# untitled2.net
KiCad netlist of a schematic drawn in EAGLE
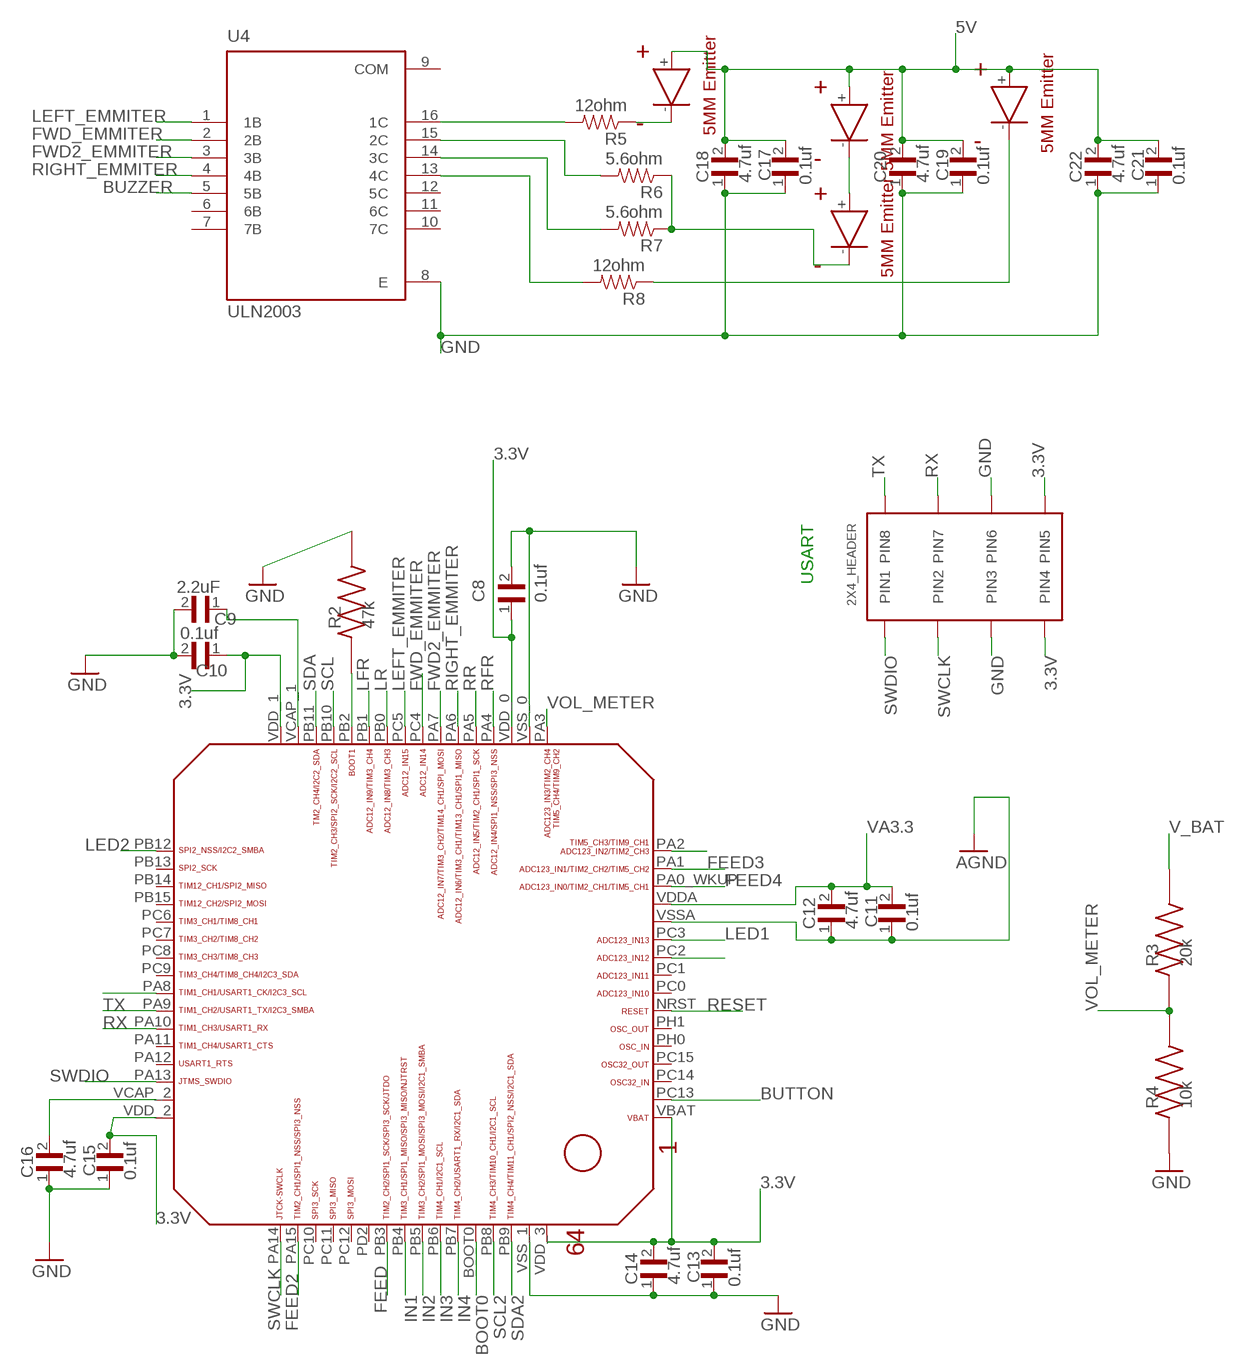
[diagram p0: schematic, sheet 1, part 1 of 2]
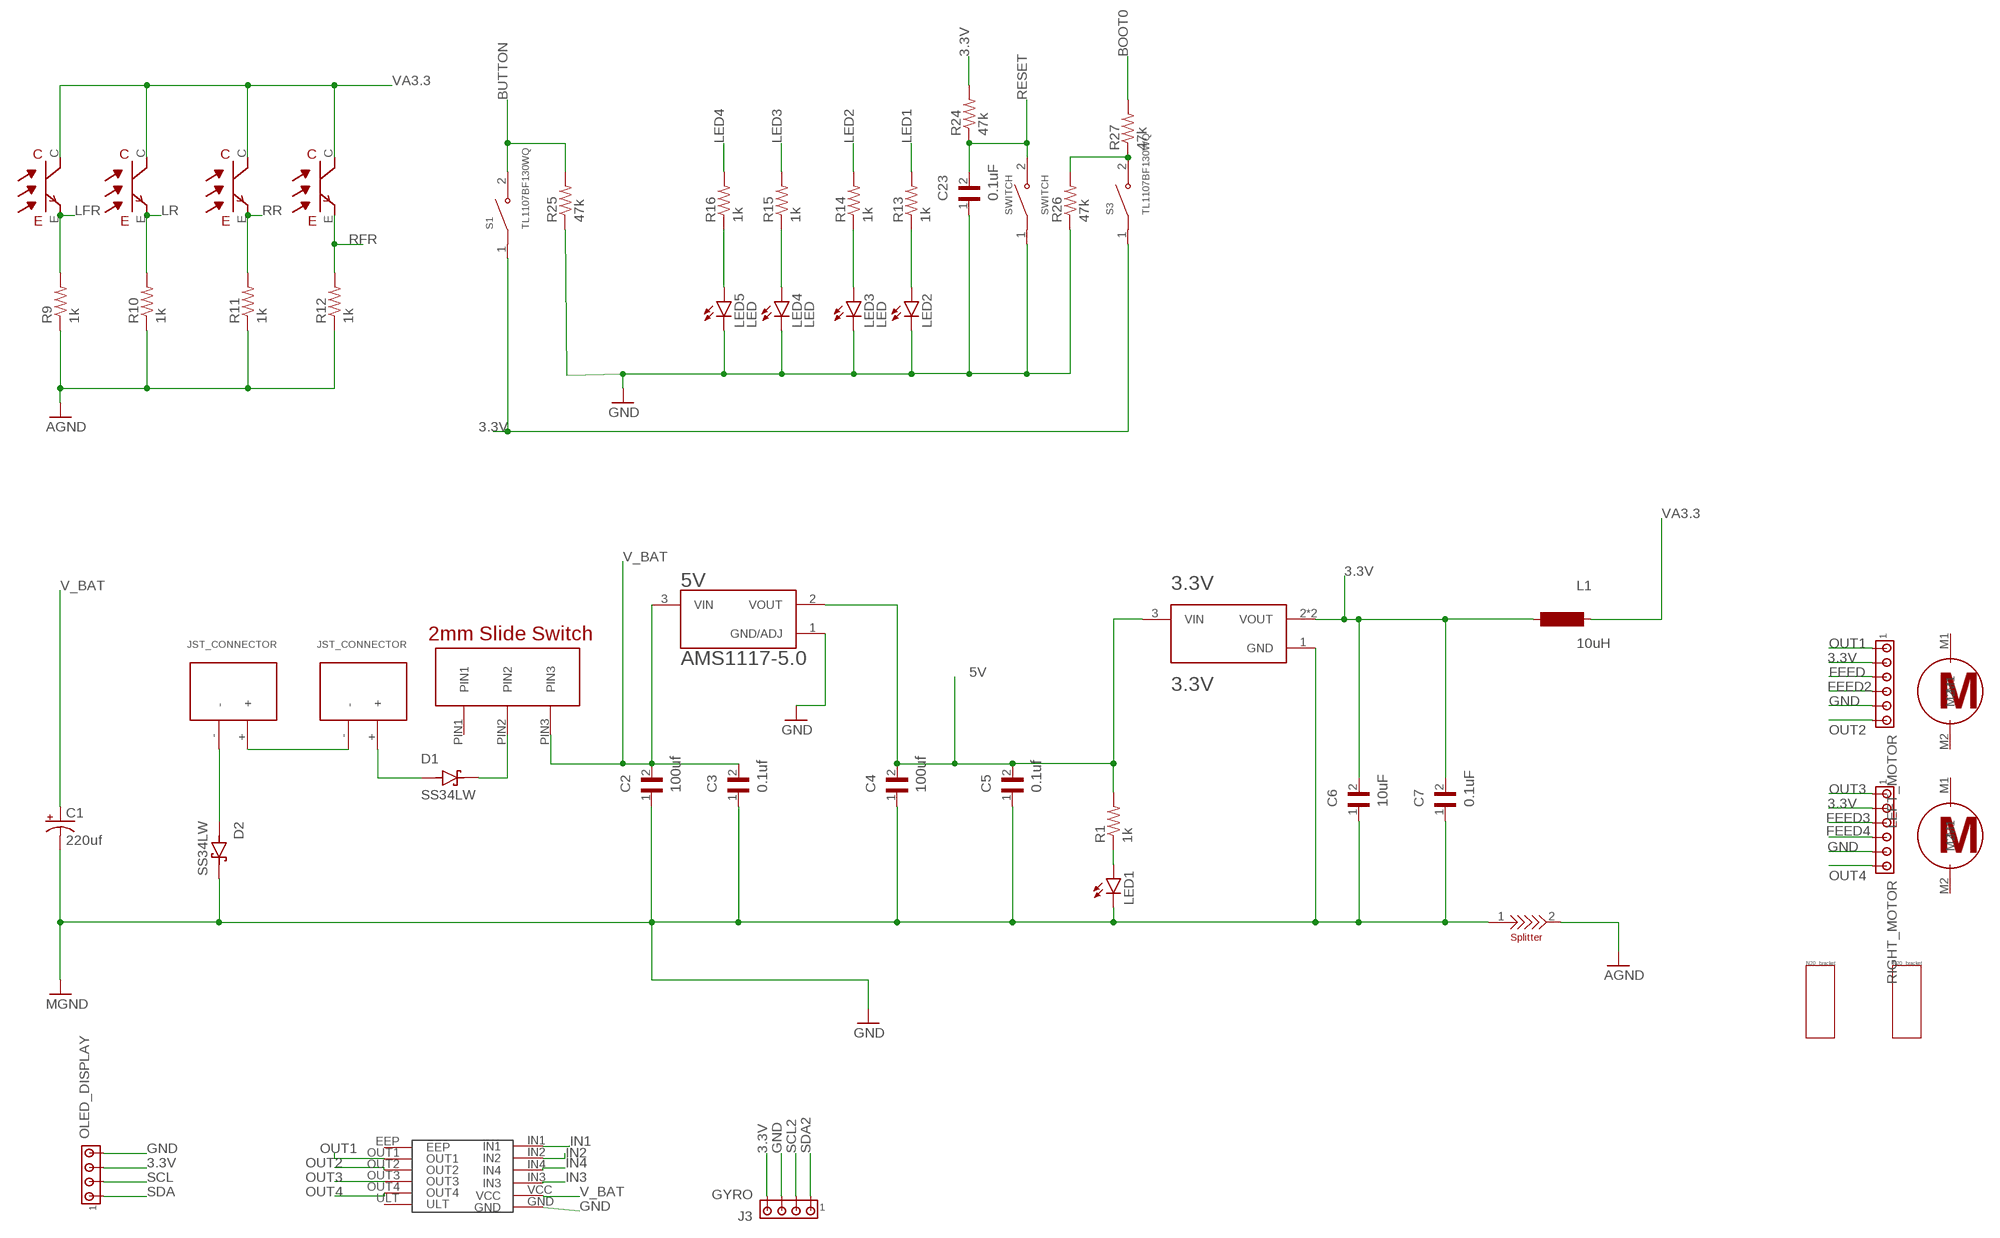
[diagram p1: schematic, sheet 1, part 2 of 2]

(export (version "E")
  (design (tool "Eeschema 10.0.6"))
  (components
    (comp (ref "3.3V")
      (value "3.3V")
      (footprint "eagle-import:SOT230P700X180-4N")
      (fields (field (name "MF") "STMicroelectronics") (field (name "MP") "LDL1117S33R"))
      (libsource (lib "eagle-import") (part "LDL1117S33R"))
    )
    (comp (ref "5V")
      (value "AMS1117-5.0")
      (footprint "eagle-import:SOT229P700X180-4N")
      (fields (field (name "MF") "Advanced Monolithic Systems"))
      (libsource (lib "eagle-import") (part "AMS1117-5.0"))
    )
    (comp (ref "C1")
      (value "220uf")
      (footprint "eagle-import:EIA3216")
      (libsource (lib "eagle-import") (part "CAP_POL1206"))
    )
    (comp (ref "C2")
      (value "100uf")
      (footprint "eagle-import:CAPC0603X35N")
      (fields (field (name "MF") "Murata") (field (name "MP") "GRM033R60J105MEA2D"))
      (libsource (lib "eagle-import") (part "GRM033R60J105MEA2D"))
    )
    (comp (ref "C3")
      (value "0.1uf")
      (footprint "eagle-import:CAPC0603X35N")
      (fields (field (name "MF") "Murata") (field (name "MP") "GRM033R60J105MEA2D"))
      (libsource (lib "eagle-import") (part "GRM033R60J105MEA2D"))
    )
    (comp (ref "C4")
      (value "100uf")
      (footprint "eagle-import:CAPC0603X35N")
      (fields (field (name "MF") "Murata") (field (name "MP") "GRM033R60J105MEA2D"))
      (libsource (lib "eagle-import") (part "GRM033R60J105MEA2D"))
    )
    (comp (ref "C5")
      (value "0.1uf")
      (footprint "eagle-import:CAPC0603X35N")
      (fields (field (name "MF") "Murata") (field (name "MP") "GRM033R60J105MEA2D"))
      (libsource (lib "eagle-import") (part "GRM033R60J105MEA2D"))
    )
    (comp (ref "C6")
      (value "10uF")
      (footprint "eagle-import:CAPC0603X35N")
      (fields (field (name "MF") "Murata") (field (name "MP") "GRM033R60J105MEA2D"))
      (libsource (lib "eagle-import") (part "GRM033R60J105MEA2D"))
    )
    (comp (ref "C7")
      (value "0.1uF")
      (footprint "eagle-import:CAPC0603X35N")
      (fields (field (name "MF") "Murata") (field (name "MP") "GRM033R60J105MEA2D"))
      (libsource (lib "eagle-import") (part "GRM033R60J105MEA2D"))
    )
    (comp (ref "C8")
      (value "0.1uf")
      (footprint "eagle-import:CAPC0603X35N")
      (fields (field (name "MF") "Murata") (field (name "MP") "GRM033R60J105MEA2D"))
      (libsource (lib "eagle-import") (part "GRM033R60J105MEA2D"))
    )
    (comp (ref "C9")
      (value "2.2uF")
      (footprint "eagle-import:CAPC0603X35N")
      (fields (field (name "MF") "Murata") (field (name "MP") "GRM033R60J105MEA2D"))
      (libsource (lib "eagle-import") (part "GRM033R60J105MEA2D"))
    )
    (comp (ref "C10")
      (value "0.1uf")
      (footprint "eagle-import:CAPC0603X35N")
      (fields (field (name "MF") "Murata") (field (name "MP") "GRM033R60J105MEA2D"))
      (libsource (lib "eagle-import") (part "GRM033R60J105MEA2D"))
    )
    (comp (ref "C11")
      (value "0.1uf")
      (footprint "eagle-import:CAPC0603X35N")
      (fields (field (name "MF") "Murata") (field (name "MP") "GRM033R60J105MEA2D"))
      (libsource (lib "eagle-import") (part "GRM033R60J105MEA2D"))
    )
    (comp (ref "C12")
      (value "4.7uf")
      (footprint "eagle-import:CAPC0603X35N")
      (fields (field (name "MF") "Murata") (field (name "MP") "GRM033R60J105MEA2D"))
      (libsource (lib "eagle-import") (part "GRM033R60J105MEA2D"))
    )
    (comp (ref "C13")
      (value "0.1uf")
      (footprint "eagle-import:CAPC0603X35N")
      (fields (field (name "MF") "Murata") (field (name "MP") "GRM033R60J105MEA2D"))
      (libsource (lib "eagle-import") (part "GRM033R60J105MEA2D"))
    )
    (comp (ref "C14")
      (value "4.7uf")
      (footprint "eagle-import:CAPC0603X35N")
      (fields (field (name "MF") "Murata") (field (name "MP") "GRM033R60J105MEA2D"))
      (libsource (lib "eagle-import") (part "GRM033R60J105MEA2D"))
    )
    (comp (ref "C15")
      (value "0.1uf")
      (footprint "eagle-import:CAPC0603X35N")
      (fields (field (name "MF") "Murata") (field (name "MP") "GRM033R60J105MEA2D"))
      (libsource (lib "eagle-import") (part "GRM033R60J105MEA2D"))
    )
    (comp (ref "C16")
      (value "4.7uf")
      (footprint "eagle-import:CAPC0603X35N")
      (fields (field (name "MF") "Murata") (field (name "MP") "GRM033R60J105MEA2D"))
      (libsource (lib "eagle-import") (part "GRM033R60J105MEA2D"))
    )
    (comp (ref "C17")
      (value "0.1uf")
      (footprint "eagle-import:CAPC0603X35N")
      (fields (field (name "MF") "Murata") (field (name "MP") "GRM033R60J105MEA2D"))
      (libsource (lib "eagle-import") (part "GRM033R60J105MEA2D"))
    )
    (comp (ref "C18")
      (value "4.7uf")
      (footprint "eagle-import:CAPC0603X35N")
      (fields (field (name "MF") "Murata") (field (name "MP") "GRM033R60J105MEA2D"))
      (libsource (lib "eagle-import") (part "GRM033R60J105MEA2D"))
    )
    (comp (ref "C19")
      (value "0.1uf")
      (footprint "eagle-import:CAPC0603X35N")
      (fields (field (name "MF") "Murata") (field (name "MP") "GRM033R60J105MEA2D"))
      (libsource (lib "eagle-import") (part "GRM033R60J105MEA2D"))
    )
    (comp (ref "C20")
      (value "4.7uf")
      (footprint "eagle-import:CAPC0603X35N")
      (fields (field (name "MF") "Murata") (field (name "MP") "GRM033R60J105MEA2D"))
      (libsource (lib "eagle-import") (part "GRM033R60J105MEA2D"))
    )
    (comp (ref "C21")
      (value "0.1uf")
      (footprint "eagle-import:CAPC0603X35N")
      (fields (field (name "MF") "Murata") (field (name "MP") "GRM033R60J105MEA2D"))
      (libsource (lib "eagle-import") (part "GRM033R60J105MEA2D"))
    )
    (comp (ref "C22")
      (value "4.7uf")
      (footprint "eagle-import:CAPC0603X35N")
      (fields (field (name "MF") "Murata") (field (name "MP") "GRM033R60J105MEA2D"))
      (libsource (lib "eagle-import") (part "GRM033R60J105MEA2D"))
    )
    (comp (ref "C23")
      (value "0.1uF")
      (footprint "eagle-import:CAPC0603X35N")
      (fields (field (name "MF") "Murata") (field (name "MP") "GRM033R60J105MEA2D"))
      (libsource (lib "eagle-import") (part "GRM033R60J105MEA2D"))
    )
    (comp (ref "D1")
      (value "SS34LW")
      (footprint "eagle-import:SODFL3718X102N")
      (fields (field (name "MF") "Taiwan Semiconductor"))
      (libsource (lib "eagle-import") (part "SS34LW"))
    )
    (comp (ref "D2")
      (value "SS34LW")
      (footprint "eagle-import:SODFL3718X102N")
      (fields (field (name "MF") "Taiwan Semiconductor"))
      (libsource (lib "eagle-import") (part "SS34LW"))
    )
    (comp (ref "EMMI1")
      (value "EMITTER")
      (footprint "eagle-import:EMITTER")
      (libsource (lib "eagle-import") (part "EMITTER"))
    )
    (comp (ref "J3")
      (value "GYRO")
      (footprint "eagle-import:10X04MTA")
      (libsource (lib "eagle-import") (part "MTA04-100"))
    )
    (comp (ref "L1")
      (value "10uH")
      (footprint "eagle-import:MS42")
      (libsource (lib "eagle-import") (part "MS42"))
    )
    (comp (ref "LED1")
      (value "LEDCHIPLED_0805")
      (footprint "eagle-import:CHIPLED_0805")
      (libsource (lib "eagle-import") (part "LEDCHIPLED_0805"))
    )
    (comp (ref "LED2")
      (value "LEDCHIPLED_0805")
      (footprint "eagle-import:CHIPLED_0805")
      (libsource (lib "eagle-import") (part "LEDCHIPLED_0805"))
    )
    (comp (ref "LED3")
      (value "LED")
      (footprint "eagle-import:CHIPLED_0805")
      (libsource (lib "eagle-import") (part "LEDCHIPLED_0805"))
    )
    (comp (ref "LED4")
      (value "LED")
      (footprint "eagle-import:CHIPLED_0805")
      (libsource (lib "eagle-import") (part "LEDCHIPLED_0805"))
    )
    (comp (ref "LED5")
      (value "LED")
      (footprint "eagle-import:CHIPLED_0805")
      (libsource (lib "eagle-import") (part "LEDCHIPLED_0805"))
    )
    (comp (ref "LEFT_MOTOR")
      (value "MTA06-100")
      (footprint "eagle-import:10X06MTA")
      (libsource (lib "eagle-import") (part "MTA06-100"))
    )
    (comp (ref "OLED_DISPLAY")
      (value "MTA04-100")
      (footprint "eagle-import:10X04MTA")
      (libsource (lib "eagle-import") (part "MTA04-100"))
    )
    (comp (ref "R1")
      (value "1k")
      (footprint "eagle-import:0603-RES")
      (libsource (lib "eagle-import") (part "RESISTOR0603-RES"))
    )
    (comp (ref "R2")
      (value "47k")
      (footprint "eagle-import:RES_ERJU01F3570C")
      (fields (field (name "MF") "Panasonic") (field (name "MP") "ERJ-U01F3570C"))
      (libsource (lib "eagle-import") (part "ERJU01F3570C"))
    )
    (comp (ref "R3")
      (value "20k")
      (footprint "eagle-import:RES_ERJU01F3570C")
      (fields (field (name "MF") "Panasonic") (field (name "MP") "ERJ-U01F3570C"))
      (libsource (lib "eagle-import") (part "ERJU01F3570C"))
    )
    (comp (ref "R4")
      (value "10k")
      (footprint "eagle-import:RES_ERJU01F3570C")
      (fields (field (name "MF") "Panasonic") (field (name "MP") "ERJ-U01F3570C"))
      (libsource (lib "eagle-import") (part "ERJU01F3570C"))
    )
    (comp (ref "R5")
      (value "12ohm")
      (footprint "eagle-import:0603-RES")
      (libsource (lib "eagle-import") (part "RESISTOR0603-RES"))
    )
    (comp (ref "R6")
      (value "5.6ohm")
      (footprint "eagle-import:0603-RES")
      (libsource (lib "eagle-import") (part "RESISTOR0603-RES"))
    )
    (comp (ref "R7")
      (value "5.6ohm")
      (footprint "eagle-import:0603-RES")
      (libsource (lib "eagle-import") (part "RESISTOR0603-RES"))
    )
    (comp (ref "R8")
      (value "12ohm")
      (footprint "eagle-import:0603-RES")
      (libsource (lib "eagle-import") (part "RESISTOR0603-RES"))
    )
    (comp (ref "R9")
      (value "1k")
      (footprint "eagle-import:0603-RES")
      (libsource (lib "eagle-import") (part "RESISTOR0603-RES"))
    )
    (comp (ref "R10")
      (value "1k")
      (footprint "eagle-import:0603-RES")
      (libsource (lib "eagle-import") (part "RESISTOR0603-RES"))
    )
    (comp (ref "R11")
      (value "1k")
      (footprint "eagle-import:0603-RES")
      (libsource (lib "eagle-import") (part "RESISTOR0603-RES"))
    )
    (comp (ref "R12")
      (value "1k")
      (footprint "eagle-import:0603-RES")
      (libsource (lib "eagle-import") (part "RESISTOR0603-RES"))
    )
    (comp (ref "R13")
      (value "1k")
      (footprint "eagle-import:0603-RES")
      (libsource (lib "eagle-import") (part "RESISTOR0603-RES"))
    )
    (comp (ref "R14")
      (value "1k")
      (footprint "eagle-import:0603-RES")
      (libsource (lib "eagle-import") (part "RESISTOR0603-RES"))
    )
    (comp (ref "R15")
      (value "1k")
      (footprint "eagle-import:0603-RES")
      (libsource (lib "eagle-import") (part "RESISTOR0603-RES"))
    )
    (comp (ref "R16")
      (value "1k")
      (footprint "eagle-import:0603-RES")
      (libsource (lib "eagle-import") (part "RESISTOR0603-RES"))
    )
    (comp (ref "R24")
      (value "47k")
      (footprint "eagle-import:0603-RES")
      (libsource (lib "eagle-import") (part "RESISTOR0603-RES"))
    )
    (comp (ref "R25")
      (value "47k")
      (footprint "eagle-import:0603-RES")
      (libsource (lib "eagle-import") (part "RESISTOR0603-RES"))
    )
    (comp (ref "R26")
      (value "47k")
      (footprint "eagle-import:0603-RES")
      (libsource (lib "eagle-import") (part "RESISTOR0603-RES"))
    )
    (comp (ref "R27")
      (value "47k")
      (footprint "eagle-import:0603-RES")
      (libsource (lib "eagle-import") (part "RESISTOR0603-RES"))
    )
    (comp (ref "RIGHT_MOTOR")
      (value "MTA06-100")
      (footprint "eagle-import:10X06MTA")
      (libsource (lib "eagle-import") (part "MTA06-100"))
    )
    (comp (ref "S1")
      (value "TL1107BF130WQ")
      (footprint "eagle-import:SW_TL1107BF130WQ")
      (fields (field (name "MF") "E-Switch"))
      (libsource (lib "eagle-import") (part "TL1107BF130WQ"))
    )
    (comp (ref "S3")
      (value "TL1107BF130WQ")
      (footprint "eagle-import:SW_TL1107BF130WQ")
      (fields (field (name "MF") "E-Switch"))
      (libsource (lib "eagle-import") (part "TL1107BF130WQ"))
    )
    (comp (ref "STM32F405RGT6")
      (value "STM32F405/415_LQFP64")
      (footprint "eagle-import:STM32F405_415_LQFP64")
      (libsource (lib "eagle-import") (part "STM32F405/415_LQFP64"))
    )
    (comp (ref "SWITCH")
      (value "SWITCH")
      (footprint "eagle-import:SW_TL1107BF130WQ")
      (fields (field (name "MF") "E-Switch") (field (name "MP") "TL1107BF130WQ"))
      (libsource (lib "eagle-import") (part "TL1107BF130WQ"))
    )
    (comp (ref "U$1")
      (value "N20_BRACKET")
      (footprint "eagle-import:BRACKER")
      (libsource (lib "eagle-import") (part "N20_BRACKET"))
    )
    (comp (ref "U$2")
      (value "MOTOR_N20")
      (footprint "eagle-import:MOTOR_N20")
      (libsource (lib "eagle-import") (part "MOTOR_N20"))
    )
    (comp (ref "U$3")
      (value "MOTOR_N20")
      (footprint "eagle-import:MOTOR_N20")
      (libsource (lib "eagle-import") (part "MOTOR_N20"))
    )
    (comp (ref "U$4")
      (value "N20_BRACKET")
      (footprint "eagle-import:BRACKER")
      (libsource (lib "eagle-import") (part "N20_BRACKET"))
    )
    (comp (ref "U$5")
      (value "JST_CONNECTOR_FEMALE")
      (footprint "eagle-import:JST_CONNECTOR_FEMALE")
      (libsource (lib "eagle-import") (part "JST_CONNECTOR_FEMALE"))
    )
    (comp (ref "U$6")
      (value "JST_CONNECTOR_FEMALE")
      (footprint "eagle-import:JST_CONNECTOR_FEMALE")
      (libsource (lib "eagle-import") (part "JST_CONNECTOR_FEMALE"))
    )
    (comp (ref "U$8")
      (value "2MMS_SLIDE_SWITCH")
      (footprint "eagle-import:2MMS_SLIDE_SWITCH")
      (libsource (lib "eagle-import") (part "2MMS_SLIDE_SWITCH"))
    )
    (comp (ref "U$9")
      (value "SPLITTER")
      (footprint "eagle-import:SPLITTER")
      (libsource (lib "eagle-import") (part "SPLITTER"))
    )
    (comp (ref "U$10")
      (value "2X3_HEADER")
      (footprint "eagle-import:2X3_HEADER")
      (libsource (lib "eagle-import") (part "2X3_HEADER"))
    )
    (comp (ref "U$11")
      (value "DRV8833")
      (footprint "eagle-import:DRV8833")
      (libsource (lib "eagle-import") (part "DRV8833"))
    )
    (comp (ref "U$12")
      (value "RECEIVER")
      (footprint "eagle-import:RECEIVER")
      (libsource (lib "eagle-import") (part "RECEIVER"))
    )
    (comp (ref "U$13")
      (value "EMITTER")
      (footprint "eagle-import:EMITTER")
      (libsource (lib "eagle-import") (part "EMITTER"))
    )
    (comp (ref "U$14")
      (value "EMITTER")
      (footprint "eagle-import:EMITTER")
      (libsource (lib "eagle-import") (part "EMITTER"))
    )
    (comp (ref "U$15")
      (value "EMITTER")
      (footprint "eagle-import:EMITTER")
      (libsource (lib "eagle-import") (part "EMITTER"))
    )
    (comp (ref "U$16")
      (value "RECEIVER")
      (footprint "eagle-import:RECEIVER")
      (libsource (lib "eagle-import") (part "RECEIVER"))
    )
    (comp (ref "U$17")
      (value "RECEIVER")
      (footprint "eagle-import:RECEIVER")
      (libsource (lib "eagle-import") (part "RECEIVER"))
    )
    (comp (ref "U$18")
      (value "RECEIVER")
      (footprint "eagle-import:RECEIVER")
      (libsource (lib "eagle-import") (part "RECEIVER"))
    )
    (comp (ref "U4")
      (value "ULN2003")
      (footprint "eagle-import:SOP65P640X120-16N")
      (fields (field (name "MF") "Texas Instruments") (field (name "MP") "ULN2003APWR"))
      (libsource (lib "eagle-import") (part "ULN2003APWR"))
    )
  )
  (nets
    (net (code "1") (name "/3.3V") (class "Default")
      (node (ref "3.3V") (pin "2") (pinfunction "VOUT_2") (pintype "output"))
      (node (ref "3.3V") (pin "4") (pinfunction "VOUT_4") (pintype "output"))
      (node (ref "C10") (pin "1") (pinfunction "1_1") (pintype "passive"))
      (node (ref "C13") (pin "2") (pinfunction "2_2") (pintype "passive"))
      (node (ref "C14") (pin "2") (pinfunction "2_2") (pintype "passive"))
      (node (ref "C15") (pin "2") (pinfunction "2_2") (pintype "passive"))
      (node (ref "C6") (pin "2") (pinfunction "2_2") (pintype "passive"))
      (node (ref "C7") (pin "2") (pinfunction "2_2") (pintype "passive"))
      (node (ref "C8") (pin "1") (pinfunction "1_1") (pintype "passive"))
      (node (ref "J3") (pin "4") (pinfunction "4_4") (pintype "passive"))
      (node (ref "L1") (pin "1") (pinfunction "1_1") (pintype "passive"))
      (node (ref "LEFT_MOTOR") (pin "2") (pinfunction "2_2") (pintype "passive"))
      (node (ref "OLED_DISPLAY") (pin "3") (pinfunction "3_3") (pintype "passive"))
      (node (ref "R24") (pin "2") (pinfunction "2_2") (pintype "passive"))
      (node (ref "RIGHT_MOTOR") (pin "2") (pinfunction "2_2") (pintype "passive"))
      (node (ref "S1") (pin "1") (pinfunction "1_1") (pintype "passive"))
      (node (ref "S3") (pin "1") (pinfunction "1_1") (pintype "passive"))
      (node (ref "STM32F405RGT6") (pin "VBAT") (pinfunction "VBAT_VBAT") (pintype "bidirectional"))
      (node (ref "STM32F405RGT6") (pin "VDD_0") (pinfunction "VDD_0_VDD_0") (pintype "bidirectional"))
      (node (ref "STM32F405RGT6") (pin "VDD_1") (pinfunction "VDD_1_VDD_1") (pintype "bidirectional"))
      (node (ref "STM32F405RGT6") (pin "VDD_2") (pinfunction "VDD_2_VDD_2") (pintype "bidirectional"))
      (node (ref "STM32F405RGT6") (pin "VDD_3") (pinfunction "VDD_3_VDD_3") (pintype "bidirectional"))
      (node (ref "U$10") (pin "PIN4") (pinfunction "PIN4_PIN4") (pintype "bidirectional"))
      (node (ref "U$10") (pin "PIN5") (pinfunction "PIN5_PIN5") (pintype "bidirectional"))
    )
    (net (code "2") (name "/5V") (class "Default")
      (node (ref "3.3V") (pin "3") (pinfunction "VIN_3") (pintype "input"))
      (node (ref "5V") (pin "2") (pinfunction "VOUT_2") (pintype "output"))
      (node (ref "C17") (pin "2") (pinfunction "2_2") (pintype "passive"))
      (node (ref "C18") (pin "2") (pinfunction "2_2") (pintype "passive"))
      (node (ref "C19") (pin "2") (pinfunction "2_2") (pintype "passive"))
      (node (ref "C20") (pin "2") (pinfunction "2_2") (pintype "passive"))
      (node (ref "C21") (pin "2") (pinfunction "2_2") (pintype "passive"))
      (node (ref "C22") (pin "2") (pinfunction "2_2") (pintype "passive"))
      (node (ref "C4") (pin "2") (pinfunction "2_2") (pintype "passive"))
      (node (ref "C5") (pin "2") (pinfunction "2_2") (pintype "passive"))
      (node (ref "EMMI1") (pin "+") (pinfunction "+_+") (pintype "bidirectional"))
      (node (ref "R1") (pin "2") (pinfunction "2_2") (pintype "passive"))
      (node (ref "U$13") (pin "+") (pinfunction "+_+") (pintype "bidirectional"))
      (node (ref "U$15") (pin "+") (pinfunction "+_+") (pintype "bidirectional"))
    )
    (net (code "3") (name "/BOOT0") (class "Default")
      (node (ref "R27") (pin "2") (pinfunction "2_2") (pintype "passive"))
      (node (ref "STM32F405RGT6") (pin "BOOT0") (pinfunction "BOOT0_BOOT0") (pintype "bidirectional"))
    )
    (net (code "4") (name "/BUTTON") (class "Default")
      (node (ref "R25") (pin "2") (pinfunction "2_2") (pintype "passive"))
      (node (ref "S1") (pin "2") (pinfunction "2_2") (pintype "passive"))
      (node (ref "STM32F405RGT6") (pin "PC13") (pinfunction "PC13_PC13") (pintype "bidirectional"))
    )
    (net (code "5") (name "/BUZZER") (class "Default")
      (node (ref "U4") (pin "5") (pinfunction "5B_5") (pintype "input"))
    )
    (net (code "6") (name "/COM") (class "Default")
      (node (ref "U4") (pin "9") (pinfunction "COM_9") (pintype "power_in"))
    )
    (net (code "7") (name "/FEED") (class "Default")
      (node (ref "LEFT_MOTOR") (pin "3") (pinfunction "3_3") (pintype "passive"))
      (node (ref "STM32F405RGT6") (pin "PB3") (pinfunction "PB3_PB3") (pintype "bidirectional"))
    )
    (net (code "8") (name "/FEED2") (class "Default")
      (node (ref "LEFT_MOTOR") (pin "4") (pinfunction "4_4") (pintype "passive"))
      (node (ref "STM32F405RGT6") (pin "PA15") (pinfunction "PA15_PA15") (pintype "bidirectional"))
    )
    (net (code "9") (name "/FEED3") (class "Default")
      (node (ref "RIGHT_MOTOR") (pin "3") (pinfunction "3_3") (pintype "passive"))
      (node (ref "STM32F405RGT6") (pin "PA1") (pinfunction "PA1_PA1") (pintype "bidirectional"))
    )
    (net (code "10") (name "/FEED4") (class "Default")
      (node (ref "RIGHT_MOTOR") (pin "4") (pinfunction "4_4") (pintype "passive"))
      (node (ref "STM32F405RGT6") (pin "PA0_WKUP") (pinfunction "PA0_AKUP_PA0_WKUP") (pintype "bidirectional"))
    )
    (net (code "11") (name "/FWD2_EMMITER") (class "Default")
      (node (ref "STM32F405RGT6") (pin "PA7") (pinfunction "PA7_PA7") (pintype "bidirectional"))
      (node (ref "U4") (pin "3") (pinfunction "3B_3") (pintype "input"))
    )
    (net (code "12") (name "/FWD_EMMITER") (class "Default")
      (node (ref "STM32F405RGT6") (pin "PC4") (pinfunction "PC4_PC4") (pintype "bidirectional"))
      (node (ref "U4") (pin "2") (pinfunction "2B_2") (pintype "input"))
    )
    (net (code "13") (name "/IN1") (class "Default")
      (node (ref "STM32F405RGT6") (pin "PB4") (pinfunction "PB4_PB4") (pintype "bidirectional"))
      (node (ref "U$11") (pin "IN1") (pinfunction "IN1_IN1") (pintype "bidirectional"))
    )
    (net (code "14") (name "/IN2") (class "Default")
      (node (ref "STM32F405RGT6") (pin "PB5") (pinfunction "PB5_PB5") (pintype "bidirectional"))
      (node (ref "U$11") (pin "IN2") (pinfunction "IN2_IN2") (pintype "bidirectional"))
    )
    (net (code "15") (name "/IN3") (class "Default")
      (node (ref "STM32F405RGT6") (pin "PB6") (pinfunction "PB6_PB6") (pintype "bidirectional"))
      (node (ref "U$11") (pin "IN3") (pinfunction "IN3_IN3") (pintype "bidirectional"))
    )
    (net (code "16") (name "/IN4") (class "Default")
      (node (ref "STM32F405RGT6") (pin "PB7") (pinfunction "PB7_PB7") (pintype "bidirectional"))
      (node (ref "U$11") (pin "IN4") (pinfunction "IN4_IN4") (pintype "bidirectional"))
    )
    (net (code "17") (name "/LED1") (class "Default")
      (node (ref "R13") (pin "2") (pinfunction "2_2") (pintype "passive"))
      (node (ref "STM32F405RGT6") (pin "PC3") (pinfunction "PC3_PC3") (pintype "bidirectional"))
    )
    (net (code "18") (name "/LED2") (class "Default")
      (node (ref "R14") (pin "2") (pinfunction "2_2") (pintype "passive"))
      (node (ref "STM32F405RGT6") (pin "PB12") (pinfunction "PB12_PB12") (pintype "bidirectional"))
    )
    (net (code "19") (name "/LED3") (class "Default")
      (node (ref "R15") (pin "2") (pinfunction "2_2") (pintype "passive"))
      (node (ref "STM32F405RGT6") (pin "PC2") (pinfunction "PC2_PC2") (pintype "bidirectional"))
    )
    (net (code "20") (name "/LED4") (class "Default")
      (node (ref "R16") (pin "2") (pinfunction "2_2") (pintype "passive"))
      (node (ref "STM32F405RGT6") (pin "PA8") (pinfunction "PA8_PA8") (pintype "bidirectional"))
    )
    (net (code "21") (name "/LEFT_EMMITER") (class "Default")
      (node (ref "STM32F405RGT6") (pin "PC5") (pinfunction "PC5_PC5") (pintype "bidirectional"))
      (node (ref "U4") (pin "1") (pinfunction "1B_1") (pintype "input"))
    )
    (net (code "22") (name "/LFR") (class "Default")
      (node (ref "R9") (pin "2") (pinfunction "2_2") (pintype "passive"))
      (node (ref "STM32F405RGT6") (pin "PB1") (pinfunction "PB1_PB1") (pintype "bidirectional"))
      (node (ref "U$18") (pin "E") (pinfunction "E_E") (pintype "bidirectional"))
    )
    (net (code "23") (name "/LR") (class "Default")
      (node (ref "R10") (pin "2") (pinfunction "2_2") (pintype "passive"))
      (node (ref "STM32F405RGT6") (pin "PB0") (pinfunction "PB0_PB0") (pintype "bidirectional"))
      (node (ref "U$17") (pin "E") (pinfunction "E_E") (pintype "bidirectional"))
    )
    (net (code "24") (name "/OUT1") (class "Default")
      (node (ref "LEFT_MOTOR") (pin "1") (pinfunction "1_1") (pintype "passive"))
      (node (ref "U$11") (pin "OUT1") (pinfunction "OUT1_OUT1") (pintype "bidirectional"))
    )
    (net (code "25") (name "/OUT2") (class "Default")
      (node (ref "LEFT_MOTOR") (pin "6") (pinfunction "6_6") (pintype "passive"))
      (node (ref "U$11") (pin "OUT2") (pinfunction "OUT2_OUT2") (pintype "bidirectional"))
    )
    (net (code "26") (name "/OUT3") (class "Default")
      (node (ref "RIGHT_MOTOR") (pin "1") (pinfunction "1_1") (pintype "passive"))
      (node (ref "U$11") (pin "OUT3") (pinfunction "OUT3_OUT3") (pintype "bidirectional"))
    )
    (net (code "27") (name "/OUT4") (class "Default")
      (node (ref "RIGHT_MOTOR") (pin "6") (pinfunction "6_6") (pintype "passive"))
      (node (ref "U$11") (pin "OUT4") (pinfunction "OUT4_OUT4") (pintype "bidirectional"))
    )
    (net (code "28") (name "/RESET") (class "Default")
      (node (ref "C23") (pin "2") (pinfunction "2_2") (pintype "passive"))
      (node (ref "R24") (pin "1") (pinfunction "1_1") (pintype "passive"))
      (node (ref "STM32F405RGT6") (pin "NRST") (pinfunction "NRST_NRST") (pintype "bidirectional"))
      (node (ref "SWITCH") (pin "2") (pinfunction "2_2") (pintype "passive"))
    )
    (net (code "29") (name "/RFR") (class "Default")
      (node (ref "R12") (pin "2") (pinfunction "2_2") (pintype "passive"))
      (node (ref "STM32F405RGT6") (pin "PA4") (pinfunction "PA4_PA4") (pintype "bidirectional"))
      (node (ref "U$12") (pin "E") (pinfunction "E_E") (pintype "bidirectional"))
    )
    (net (code "30") (name "/RIGHT_EMMITER") (class "Default")
      (node (ref "STM32F405RGT6") (pin "PA6") (pinfunction "PA6_PA6") (pintype "bidirectional"))
      (node (ref "U4") (pin "4") (pinfunction "4B_4") (pintype "input"))
    )
    (net (code "31") (name "/RR") (class "Default")
      (node (ref "R11") (pin "2") (pinfunction "2_2") (pintype "passive"))
      (node (ref "STM32F405RGT6") (pin "PA5") (pinfunction "PA5_PA5") (pintype "bidirectional"))
      (node (ref "U$16") (pin "E") (pinfunction "E_E") (pintype "bidirectional"))
    )
    (net (code "32") (name "/RX") (class "Default")
      (node (ref "STM32F405RGT6") (pin "PA10") (pinfunction "PA10_PA10") (pintype "bidirectional"))
      (node (ref "U$10") (pin "PIN7") (pinfunction "PIN7_PIN7") (pintype "bidirectional"))
    )
    (net (code "33") (name "/SCL") (class "Default")
      (node (ref "OLED_DISPLAY") (pin "2") (pinfunction "2_2") (pintype "passive"))
      (node (ref "STM32F405RGT6") (pin "PB10") (pinfunction "PB10_PB10") (pintype "bidirectional"))
    )
    (net (code "34") (name "/SCL2") (class "Default")
      (node (ref "J3") (pin "2") (pinfunction "2_2") (pintype "passive"))
      (node (ref "STM32F405RGT6") (pin "PB8") (pinfunction "PB8_PB8") (pintype "bidirectional"))
    )
    (net (code "35") (name "/SDA") (class "Default")
      (node (ref "OLED_DISPLAY") (pin "1") (pinfunction "1_1") (pintype "passive"))
      (node (ref "STM32F405RGT6") (pin "PB11") (pinfunction "PB11_PB11") (pintype "bidirectional"))
    )
    (net (code "36") (name "/SDA2") (class "Default")
      (node (ref "J3") (pin "1") (pinfunction "1_1") (pintype "passive"))
      (node (ref "STM32F405RGT6") (pin "PB9") (pinfunction "PB9_PB9") (pintype "bidirectional"))
    )
    (net (code "37") (name "/SWCLK") (class "Default")
      (node (ref "STM32F405RGT6") (pin "PA14") (pinfunction "PA14_PA14") (pintype "bidirectional"))
      (node (ref "U$10") (pin "PIN2") (pinfunction "PIN2_PIN2") (pintype "bidirectional"))
    )
    (net (code "38") (name "/SWDIO") (class "Default")
      (node (ref "STM32F405RGT6") (pin "PA13") (pinfunction "PA13_PA13") (pintype "bidirectional"))
      (node (ref "U$10") (pin "PIN1") (pinfunction "PIN1_PIN1") (pintype "bidirectional"))
    )
    (net (code "39") (name "/TX") (class "Default")
      (node (ref "STM32F405RGT6") (pin "PA9") (pinfunction "PA9_PA9") (pintype "bidirectional"))
      (node (ref "U$10") (pin "PIN8") (pinfunction "PIN8_PIN8") (pintype "bidirectional"))
    )
    (net (code "40") (name "/VA3.3") (class "Default")
      (node (ref "C11") (pin "2") (pinfunction "2_2") (pintype "passive"))
      (node (ref "C12") (pin "2") (pinfunction "2_2") (pintype "passive"))
      (node (ref "L1") (pin "2") (pinfunction "2_2") (pintype "passive"))
      (node (ref "STM32F405RGT6") (pin "VDDA") (pinfunction "VDDA_VDDA") (pintype "bidirectional"))
      (node (ref "U$12") (pin "C") (pinfunction "C_C") (pintype "bidirectional"))
      (node (ref "U$16") (pin "C") (pinfunction "C_C") (pintype "bidirectional"))
      (node (ref "U$17") (pin "C") (pinfunction "C_C") (pintype "bidirectional"))
      (node (ref "U$18") (pin "C") (pinfunction "C_C") (pintype "bidirectional"))
    )
    (net (code "41") (name "/VOL_METER") (class "Default")
      (node (ref "R3") (pin "1") (pinfunction "1_1") (pintype "passive"))
      (node (ref "R4") (pin "2") (pinfunction "2_2") (pintype "passive"))
      (node (ref "STM32F405RGT6") (pin "PA3") (pinfunction "PA3_PA3") (pintype "bidirectional"))
    )
    (net (code "42") (name "/V_BAT") (class "Default")
      (node (ref "5V") (pin "3") (pinfunction "VIN_3") (pintype "input"))
      (node (ref "C1") (pin "A") (pinfunction "+_A") (pintype "passive"))
      (node (ref "C2") (pin "2") (pinfunction "2_2") (pintype "passive"))
      (node (ref "C3") (pin "2") (pinfunction "2_2") (pintype "passive"))
      (node (ref "R3") (pin "2") (pinfunction "2_2") (pintype "passive"))
      (node (ref "U$11") (pin "VCC") (pinfunction "VCC_VCC") (pintype "bidirectional"))
      (node (ref "U$8") (pin "PIN3") (pinfunction "PIN3_PIN3") (pintype "bidirectional"))
    )
    (net (code "43") (name "AGND") (class "Default")
      (node (ref "3.3V") (pin "1") (pinfunction "GND_1") (pintype "power_in"))
      (node (ref "5V") (pin "1") (pinfunction "GND/ADJ_1") (pintype "power_in"))
      (node (ref "C1") (pin "C") (pinfunction "-_C") (pintype "passive"))
      (node (ref "C10") (pin "2") (pinfunction "2_2") (pintype "passive"))
      (node (ref "C11") (pin "1") (pinfunction "1_1") (pintype "passive"))
      (node (ref "C12") (pin "1") (pinfunction "1_1") (pintype "passive"))
      (node (ref "C13") (pin "1") (pinfunction "1_1") (pintype "passive"))
      (node (ref "C14") (pin "1") (pinfunction "1_1") (pintype "passive"))
      (node (ref "C15") (pin "1") (pinfunction "1_1") (pintype "passive"))
      (node (ref "C16") (pin "1") (pinfunction "1_1") (pintype "passive"))
      (node (ref "C17") (pin "1") (pinfunction "1_1") (pintype "passive"))
      (node (ref "C18") (pin "1") (pinfunction "1_1") (pintype "passive"))
      (node (ref "C19") (pin "1") (pinfunction "1_1") (pintype "passive"))
      (node (ref "C2") (pin "1") (pinfunction "1_1") (pintype "passive"))
      (node (ref "C20") (pin "1") (pinfunction "1_1") (pintype "passive"))
      (node (ref "C21") (pin "1") (pinfunction "1_1") (pintype "passive"))
      (node (ref "C22") (pin "1") (pinfunction "1_1") (pintype "passive"))
      (node (ref "C23") (pin "1") (pinfunction "1_1") (pintype "passive"))
      (node (ref "C3") (pin "1") (pinfunction "1_1") (pintype "passive"))
      (node (ref "C4") (pin "1") (pinfunction "1_1") (pintype "passive"))
      (node (ref "C5") (pin "1") (pinfunction "1_1") (pintype "passive"))
      (node (ref "C6") (pin "1") (pinfunction "1_1") (pintype "passive"))
      (node (ref "C7") (pin "1") (pinfunction "1_1") (pintype "passive"))
      (node (ref "C8") (pin "2") (pinfunction "2_2") (pintype "passive"))
      (node (ref "C9") (pin "2") (pinfunction "2_2") (pintype "passive"))
      (node (ref "D2") (pin "C") (pinfunction "K_C") (pintype "passive"))
      (node (ref "J3") (pin "3") (pinfunction "3_3") (pintype "passive"))
      (node (ref "LED1") (pin "C") (pinfunction "C_C") (pintype "passive"))
      (node (ref "LED2") (pin "C") (pinfunction "C_C") (pintype "passive"))
      (node (ref "LED3") (pin "C") (pinfunction "C_C") (pintype "passive"))
      (node (ref "LED4") (pin "C") (pinfunction "C_C") (pintype "passive"))
      (node (ref "LED5") (pin "C") (pinfunction "C_C") (pintype "passive"))
      (node (ref "LEFT_MOTOR") (pin "5") (pinfunction "5_5") (pintype "passive"))
      (node (ref "OLED_DISPLAY") (pin "4") (pinfunction "4_4") (pintype "passive"))
      (node (ref "R10") (pin "1") (pinfunction "1_1") (pintype "passive"))
      (node (ref "R11") (pin "1") (pinfunction "1_1") (pintype "passive"))
      (node (ref "R12") (pin "1") (pinfunction "1_1") (pintype "passive"))
      (node (ref "R2") (pin "2") (pinfunction "2_2") (pintype "passive"))
      (node (ref "R25") (pin "1") (pinfunction "1_1") (pintype "passive"))
      (node (ref "R26") (pin "1") (pinfunction "1_1") (pintype "passive"))
      (node (ref "R4") (pin "1") (pinfunction "1_1") (pintype "passive"))
      (node (ref "R9") (pin "1") (pinfunction "1_1") (pintype "passive"))
      (node (ref "RIGHT_MOTOR") (pin "5") (pinfunction "5_5") (pintype "passive"))
      (node (ref "STM32F405RGT6") (pin "VSSA") (pinfunction "VSSA_VSSA") (pintype "bidirectional"))
      (node (ref "STM32F405RGT6") (pin "VSS_0") (pinfunction "VSS_0_VSS_0") (pintype "bidirectional"))
      (node (ref "STM32F405RGT6") (pin "VSS_1") (pinfunction "VSS_1_VSS_1") (pintype "bidirectional"))
      (node (ref "SWITCH") (pin "1") (pinfunction "1_1") (pintype "passive"))
      (node (ref "U$10") (pin "PIN3") (pinfunction "PIN3_PIN3") (pintype "bidirectional"))
      (node (ref "U$10") (pin "PIN6") (pinfunction "PIN6_PIN6") (pintype "bidirectional"))
      (node (ref "U$11") (pin "GND") (pinfunction "GND_GND") (pintype "bidirectional"))
      (node (ref "U$9") (pin "1") (pinfunction "1_1") (pintype "bidirectional"))
      (node (ref "U$9") (pin "2") (pinfunction "2_2") (pintype "bidirectional"))
      (node (ref "U4") (pin "8") (pinfunction "E_8") (pintype "power_in"))
    )
    (net (code "44") (name "Net-(C9-Pad1)") (class "Default")
      (node (ref "C9") (pin "1") (pinfunction "1_1") (pintype "passive"))
      (node (ref "STM32F405RGT6") (pin "VCAP_1") (pinfunction "VCAP_1_VCAP_1") (pintype "bidirectional"))
    )
    (net (code "45") (name "Net-(C16-Pad2)") (class "Default")
      (node (ref "C16") (pin "2") (pinfunction "2_2") (pintype "passive"))
      (node (ref "STM32F405RGT6") (pin "VCAP_2") (pinfunction "VCAP_2_VCAP_2") (pintype "bidirectional"))
    )
    (net (code "46") (name "Net-(D1-K)") (class "Default")
      (node (ref "D1") (pin "C") (pinfunction "K_C") (pintype "passive"))
      (node (ref "U$8") (pin "PIN2") (pinfunction "PIN2_PIN2") (pintype "bidirectional"))
    )
    (net (code "47") (name "Net-(D1-PadA)") (class "Default")
      (node (ref "D1") (pin "A") (pinfunction "A_A") (pintype "passive"))
      (node (ref "U$6") (pin "+") (pinfunction "+_+") (pintype "bidirectional"))
    )
    (net (code "48") (name "Net-(D2-PadA)") (class "Default")
      (node (ref "D2") (pin "A") (pinfunction "A_A") (pintype "passive"))
      (node (ref "U$5") (pin "-") (pinfunction "-_-") (pintype "bidirectional"))
    )
    (net (code "49") (name "Net-(EMMI1-Pad-)") (class "Default")
      (node (ref "EMMI1") (pin "-") (pinfunction "-_-") (pintype "bidirectional"))
      (node (ref "R5") (pin "1") (pinfunction "1_1") (pintype "passive"))
    )
    (net (code "50") (name "Net-(LED1-PadA)") (class "Default")
      (node (ref "LED1") (pin "A") (pinfunction "A_A") (pintype "passive"))
      (node (ref "R1") (pin "1") (pinfunction "1_1") (pintype "passive"))
    )
    (net (code "51") (name "Net-(LED2-PadA)") (class "Default")
      (node (ref "LED2") (pin "A") (pinfunction "A_A") (pintype "passive"))
      (node (ref "R13") (pin "1") (pinfunction "1_1") (pintype "passive"))
    )
    (net (code "52") (name "Net-(LED3-PadA)") (class "Default")
      (node (ref "LED3") (pin "A") (pinfunction "A_A") (pintype "passive"))
      (node (ref "R14") (pin "1") (pinfunction "1_1") (pintype "passive"))
    )
    (net (code "53") (name "Net-(LED4-PadA)") (class "Default")
      (node (ref "LED4") (pin "A") (pinfunction "A_A") (pintype "passive"))
      (node (ref "R15") (pin "1") (pinfunction "1_1") (pintype "passive"))
    )
    (net (code "54") (name "Net-(LED5-PadA)") (class "Default")
      (node (ref "LED5") (pin "A") (pinfunction "A_A") (pintype "passive"))
      (node (ref "R16") (pin "1") (pinfunction "1_1") (pintype "passive"))
    )
    (net (code "55") (name "Net-(R2-Pad1)") (class "Default")
      (node (ref "R2") (pin "1") (pinfunction "1_1") (pintype "passive"))
      (node (ref "STM32F405RGT6") (pin "PB2") (pinfunction "PB2_PB2") (pintype "bidirectional"))
    )
    (net (code "56") (name "Net-(R6-Pad1)") (class "Default")
      (node (ref "R6") (pin "1") (pinfunction "1_1") (pintype "passive"))
      (node (ref "R7") (pin "1") (pinfunction "1_1") (pintype "passive"))
      (node (ref "U$14") (pin "-") (pinfunction "-_-") (pintype "bidirectional"))
    )
    (net (code "57") (name "Net-(R8-Pad1)") (class "Default")
      (node (ref "R8") (pin "1") (pinfunction "1_1") (pintype "passive"))
      (node (ref "U$15") (pin "-") (pinfunction "-_-") (pintype "bidirectional"))
    )
    (net (code "58") (name "Net-(R26-Pad2)") (class "Default")
      (node (ref "R26") (pin "2") (pinfunction "2_2") (pintype "passive"))
      (node (ref "R27") (pin "1") (pinfunction "1_1") (pintype "passive"))
      (node (ref "S3") (pin "2") (pinfunction "2_2") (pintype "passive"))
    )
    (net (code "59") (name "Net-(U$5-Pad+)") (class "Default")
      (node (ref "U$5") (pin "+") (pinfunction "+_+") (pintype "bidirectional"))
      (node (ref "U$6") (pin "-") (pinfunction "-_-") (pintype "bidirectional"))
    )
    (net (code "60") (name "Net-(U$13-Pad-)") (class "Default")
      (node (ref "U$13") (pin "-") (pinfunction "-_-") (pintype "bidirectional"))
      (node (ref "U$14") (pin "+") (pinfunction "+_+") (pintype "bidirectional"))
    )
    (net (code "61") (name "Net-(U4-1C)") (class "Default")
      (node (ref "R5") (pin "2") (pinfunction "2_2") (pintype "passive"))
      (node (ref "U4") (pin "16") (pinfunction "1C_16") (pintype "output"))
    )
    (net (code "62") (name "Net-(U4-2C)") (class "Default")
      (node (ref "R6") (pin "2") (pinfunction "2_2") (pintype "passive"))
      (node (ref "U4") (pin "15") (pinfunction "2C_15") (pintype "output"))
    )
    (net (code "63") (name "Net-(U4-3C)") (class "Default")
      (node (ref "R7") (pin "2") (pinfunction "2_2") (pintype "passive"))
      (node (ref "U4") (pin "14") (pinfunction "3C_14") (pintype "output"))
    )
    (net (code "64") (name "Net-(U4-4C)") (class "Default")
      (node (ref "R8") (pin "2") (pinfunction "2_2") (pintype "passive"))
      (node (ref "U4") (pin "13") (pinfunction "4C_13") (pintype "output"))
    )
    (net (code "65") (name "unconnected-(STM32F405RGT6-PadPA2)") (class "Default")
      (node (ref "STM32F405RGT6") (pin "PA2") (pinfunction "PA2_PA2") (pintype "bidirectional"))
    )
    (net (code "66") (name "unconnected-(STM32F405RGT6-PadPA11)") (class "Default")
      (node (ref "STM32F405RGT6") (pin "PA11") (pinfunction "PA11_PA11") (pintype "bidirectional"))
    )
    (net (code "67") (name "unconnected-(STM32F405RGT6-PadPA12)") (class "Default")
      (node (ref "STM32F405RGT6") (pin "PA12") (pinfunction "PA12_PA12") (pintype "bidirectional"))
    )
    (net (code "68") (name "unconnected-(STM32F405RGT6-PadPB13)") (class "Default")
      (node (ref "STM32F405RGT6") (pin "PB13") (pinfunction "PB13_PB13") (pintype "bidirectional"))
    )
    (net (code "69") (name "unconnected-(STM32F405RGT6-PadPB14)") (class "Default")
      (node (ref "STM32F405RGT6") (pin "PB14") (pinfunction "PB14_PB14") (pintype "bidirectional"))
    )
    (net (code "70") (name "unconnected-(STM32F405RGT6-PadPB15)") (class "Default")
      (node (ref "STM32F405RGT6") (pin "PB15") (pinfunction "PB15_PB15") (pintype "bidirectional"))
    )
    (net (code "71") (name "unconnected-(STM32F405RGT6-PadPC0)") (class "Default")
      (node (ref "STM32F405RGT6") (pin "PC0") (pinfunction "PC0_PC0") (pintype "bidirectional"))
    )
    (net (code "72") (name "unconnected-(STM32F405RGT6-PadPC1)") (class "Default")
      (node (ref "STM32F405RGT6") (pin "PC1") (pinfunction "PC1_PC1") (pintype "bidirectional"))
    )
    (net (code "73") (name "unconnected-(STM32F405RGT6-PadPC6)") (class "Default")
      (node (ref "STM32F405RGT6") (pin "PC6") (pinfunction "PC6_PC6") (pintype "bidirectional"))
    )
    (net (code "74") (name "unconnected-(STM32F405RGT6-PadPC7)") (class "Default")
      (node (ref "STM32F405RGT6") (pin "PC7") (pinfunction "PC7_PC7") (pintype "bidirectional"))
    )
    (net (code "75") (name "unconnected-(STM32F405RGT6-PadPC8)") (class "Default")
      (node (ref "STM32F405RGT6") (pin "PC8") (pinfunction "PC8_PC8") (pintype "bidirectional"))
    )
    (net (code "76") (name "unconnected-(STM32F405RGT6-PadPC9)") (class "Default")
      (node (ref "STM32F405RGT6") (pin "PC9") (pinfunction "PC9_PC9") (pintype "bidirectional"))
    )
    (net (code "77") (name "unconnected-(STM32F405RGT6-PadPC10)") (class "Default")
      (node (ref "STM32F405RGT6") (pin "PC10") (pinfunction "PC10_PC10") (pintype "bidirectional"))
    )
    (net (code "78") (name "unconnected-(STM32F405RGT6-PadPC11)") (class "Default")
      (node (ref "STM32F405RGT6") (pin "PC11") (pinfunction "PC11_PC11") (pintype "bidirectional"))
    )
    (net (code "79") (name "unconnected-(STM32F405RGT6-PadPC12)") (class "Default")
      (node (ref "STM32F405RGT6") (pin "PC12") (pinfunction "PC12_PC12") (pintype "bidirectional"))
    )
    (net (code "80") (name "unconnected-(STM32F405RGT6-PadPC14)") (class "Default")
      (node (ref "STM32F405RGT6") (pin "PC14") (pinfunction "PC14_PC14") (pintype "bidirectional"))
    )
    (net (code "81") (name "unconnected-(STM32F405RGT6-PadPC15)") (class "Default")
      (node (ref "STM32F405RGT6") (pin "PC15") (pinfunction "PC15_PC15") (pintype "bidirectional"))
    )
    (net (code "82") (name "unconnected-(STM32F405RGT6-PadPD2)") (class "Default")
      (node (ref "STM32F405RGT6") (pin "PD2") (pinfunction "PD2_PD2") (pintype "bidirectional"))
    )
    (net (code "83") (name "unconnected-(STM32F405RGT6-PadPH0)") (class "Default")
      (node (ref "STM32F405RGT6") (pin "PH0") (pinfunction "PH0_PH0") (pintype "bidirectional"))
    )
    (net (code "84") (name "unconnected-(STM32F405RGT6-PadPH1)") (class "Default")
      (node (ref "STM32F405RGT6") (pin "PH1") (pinfunction "PH1_PH1") (pintype "bidirectional"))
    )
    (net (code "85") (name "unconnected-(U$2-PadM1)") (class "Default")
      (node (ref "U$2") (pin "M1") (pinfunction "M1_M1") (pintype "bidirectional"))
    )
    (net (code "86") (name "unconnected-(U$2-PadM2)") (class "Default")
      (node (ref "U$2") (pin "M2") (pinfunction "M2_M2") (pintype "bidirectional"))
    )
    (net (code "87") (name "unconnected-(U$3-PadM1)") (class "Default")
      (node (ref "U$3") (pin "M1") (pinfunction "M1_M1") (pintype "bidirectional"))
    )
    (net (code "88") (name "unconnected-(U$3-PadM2)") (class "Default")
      (node (ref "U$3") (pin "M2") (pinfunction "M2_M2") (pintype "bidirectional"))
    )
    (net (code "89") (name "unconnected-(U$8-PadPIN1)") (class "Default")
      (node (ref "U$8") (pin "PIN1") (pinfunction "PIN1_PIN1") (pintype "bidirectional"))
    )
    (net (code "90") (name "unconnected-(U$11-PadEEP)") (class "Default")
      (node (ref "U$11") (pin "EEP") (pinfunction "EEP_EEP") (pintype "bidirectional"))
    )
    (net (code "91") (name "unconnected-(U$11-PadULT)") (class "Default")
      (node (ref "U$11") (pin "ULT") (pinfunction "ULT_ULT") (pintype "bidirectional"))
    )
    (net (code "92") (name "unconnected-(U4-5C-Pad12)") (class "Default")
      (node (ref "U4") (pin "12") (pinfunction "5C_12") (pintype "output"))
    )
    (net (code "93") (name "unconnected-(U4-6B-Pad6)") (class "Default")
      (node (ref "U4") (pin "6") (pinfunction "6B_6") (pintype "input"))
    )
    (net (code "94") (name "unconnected-(U4-6C-Pad11)") (class "Default")
      (node (ref "U4") (pin "11") (pinfunction "6C_11") (pintype "output"))
    )
    (net (code "95") (name "unconnected-(U4-7B-Pad7)") (class "Default")
      (node (ref "U4") (pin "7") (pinfunction "7B_7") (pintype "input"))
    )
    (net (code "96") (name "unconnected-(U4-7C-Pad10)") (class "Default")
      (node (ref "U4") (pin "10") (pinfunction "7C_10") (pintype "output"))
    )
  )
)
